# backlight_board.net
KiCad netlist of a schematic drawn in EAGLE
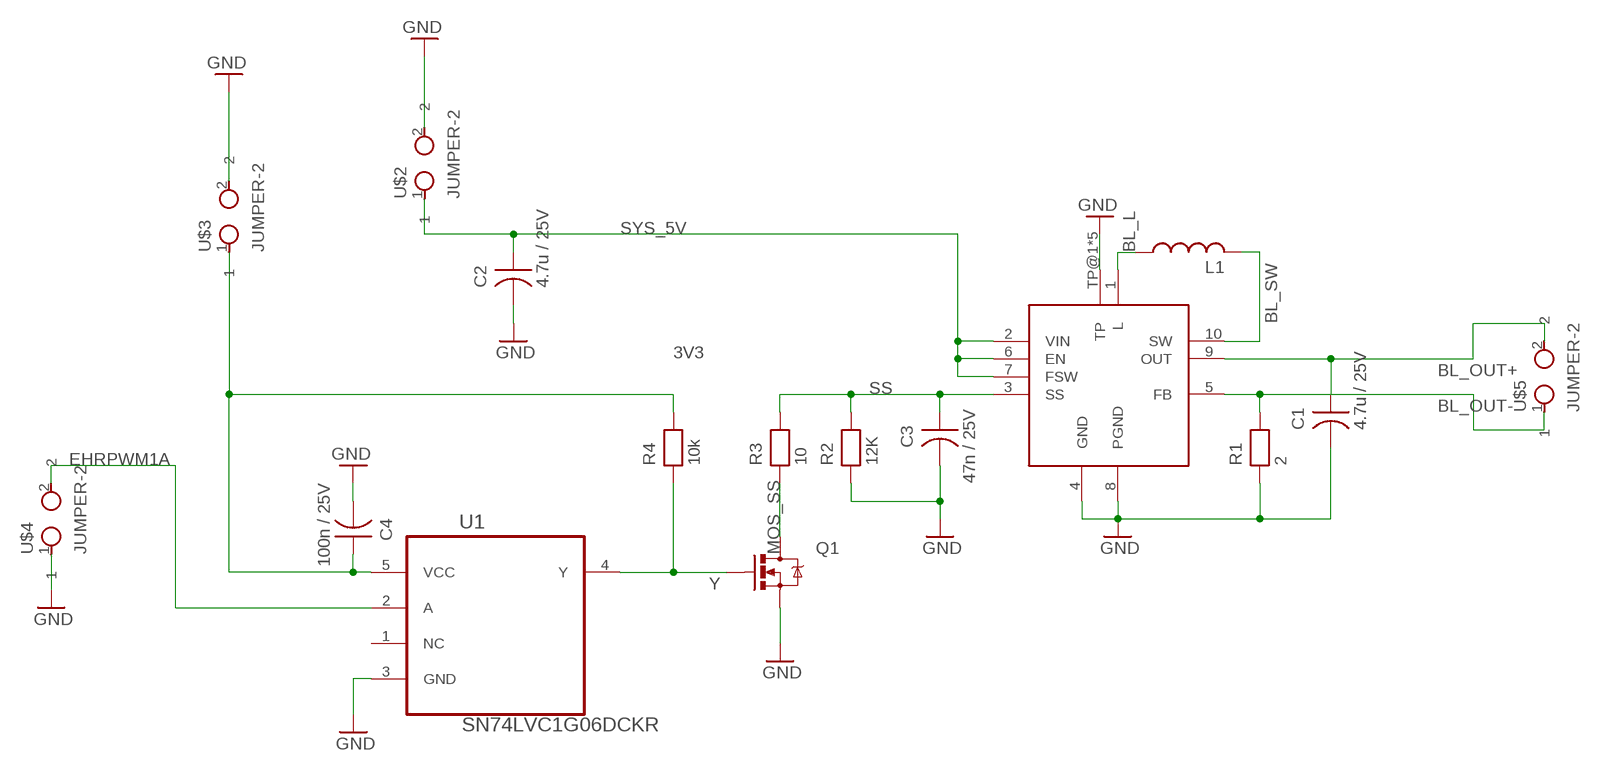
[diagram p0: schematic, sheet 1]

(export (version "E")
  (design (tool "Eeschema 10.0.6"))
  (components
    (comp (ref "C1")
      (value "4.7u / 25V")
      (footprint "eagle-import:R0805")
      (libsource (lib "eagle-import") (part "PCAP0805LEVEL3"))
    )
    (comp (ref "C2")
      (value "4.7u / 25V")
      (footprint "eagle-import:R0805")
      (libsource (lib "eagle-import") (part "PCAP0805LEVEL3"))
    )
    (comp (ref "C3")
      (value "47n / 25V")
      (footprint "eagle-import:R0603")
      (libsource (lib "eagle-import") (part "PCAP0603LEVEL3"))
    )
    (comp (ref "C4")
      (value "100n / 25V")
      (footprint "eagle-import:R0603")
      (libsource (lib "eagle-import") (part "PCAP0603LEVEL3"))
    )
    (comp (ref "L1")
      (value "L-US")
      (footprint "eagle-import:VLCF4018-2")
      (libsource (lib "eagle-import") (part "L-US"))
    )
    (comp (ref "Q1")
      (value "MOSFET-NCHANNELBSS138")
      (footprint "eagle-import:SOT23")
      (libsource (lib "eagle-import") (part "MOSFET-NCHANNELBSS138"))
    )
    (comp (ref "R1")
      (value "2")
      (footprint "eagle-import:R0603")
      (libsource (lib "eagle-import") (part "PRES0603LEVEL3"))
    )
    (comp (ref "R2")
      (value "12K")
      (footprint "eagle-import:R0603")
      (libsource (lib "eagle-import") (part "PRES0603LEVEL3"))
    )
    (comp (ref "R3")
      (value "10")
      (footprint "eagle-import:R0603")
      (libsource (lib "eagle-import") (part "PRES0603LEVEL3"))
    )
    (comp (ref "R4")
      (value "10k")
      (footprint "eagle-import:R0603")
      (libsource (lib "eagle-import") (part "PRES0603LEVEL3"))
    )
    (comp (ref "U$1")
      (value "TPS61080")
      (footprint "eagle-import:VSON-10")
      (libsource (lib "eagle-import") (part "TPS61080"))
    )
    (comp (ref "U$2")
      (value "JUMPER-2")
      (footprint "eagle-import:1X02")
      (libsource (lib "eagle-import") (part "JUMPER-2"))
    )
    (comp (ref "U$3")
      (value "JUMPER-2")
      (footprint "eagle-import:1X02")
      (libsource (lib "eagle-import") (part "JUMPER-2"))
    )
    (comp (ref "U$4")
      (value "JUMPER-2")
      (footprint "eagle-import:1X02")
      (libsource (lib "eagle-import") (part "JUMPER-2"))
    )
    (comp (ref "U$5")
      (value "JUMPER-2")
      (footprint "eagle-import:1X02")
      (libsource (lib "eagle-import") (part "JUMPER-2"))
    )
    (comp (ref "U1")
      (value "SN74LVC1G06DCKR")
      (footprint "eagle-import:SOT65P210X110-5N")
      (libsource (lib "eagle-import") (part "SN74LVC1G06DCKR"))
    )
  )
  (nets
    (net (code "1") (name "/3V3") (class "Default")
      (node (ref "C4") (pin "P$2") (pinfunction "P$2_P$2") (pintype "bidirectional"))
      (node (ref "R4") (pin "P$2") (pinfunction "P$2_P$2") (pintype "bidirectional"))
      (node (ref "U$3") (pin "1") (pinfunction "1_1") (pintype "bidirectional"))
      (node (ref "U1") (pin "5") (pinfunction "VCC_5") (pintype "power_in"))
    )
    (net (code "2") (name "/BL_L") (class "Default")
      (node (ref "L1") (pin "1") (pinfunction "1_1") (pintype "passive"))
      (node (ref "U$1") (pin "1") (pinfunction "L_1") (pintype "bidirectional"))
    )
    (net (code "3") (name "/BL_OUT+") (class "Default")
      (node (ref "C1") (pin "P$2") (pinfunction "P$2_P$2") (pintype "bidirectional"))
      (node (ref "U$1") (pin "9") (pinfunction "OUT_9") (pintype "bidirectional"))
      (node (ref "U$5") (pin "2") (pinfunction "2_2") (pintype "bidirectional"))
    )
    (net (code "4") (name "/BL_OUT-") (class "Default")
      (node (ref "R1") (pin "P$2") (pinfunction "P$2_P$2") (pintype "bidirectional"))
      (node (ref "U$1") (pin "5") (pinfunction "FB_5") (pintype "bidirectional"))
      (node (ref "U$5") (pin "1") (pinfunction "1_1") (pintype "bidirectional"))
    )
    (net (code "5") (name "/BL_SW") (class "Default")
      (node (ref "L1") (pin "2") (pinfunction "2_2") (pintype "passive"))
      (node (ref "U$1") (pin "10") (pinfunction "SW_10") (pintype "bidirectional"))
    )
    (net (code "6") (name "/EHRPWM1A") (class "Default")
      (node (ref "U$4") (pin "2") (pinfunction "2_2") (pintype "bidirectional"))
      (node (ref "U1") (pin "2") (pinfunction "A_2") (pintype "input"))
    )
    (net (code "7") (name "/MOS_SS") (class "Default")
      (node (ref "Q1") (pin "3") (pinfunction "D_3") (pintype "passive"))
      (node (ref "R3") (pin "P$1") (pinfunction "P$1_P$1") (pintype "bidirectional"))
    )
    (net (code "8") (name "/SS") (class "Default")
      (node (ref "C3") (pin "P$2") (pinfunction "P$2_P$2") (pintype "bidirectional"))
      (node (ref "R2") (pin "P$2") (pinfunction "P$2_P$2") (pintype "bidirectional"))
      (node (ref "R3") (pin "P$2") (pinfunction "P$2_P$2") (pintype "bidirectional"))
      (node (ref "U$1") (pin "3") (pinfunction "SS_3") (pintype "bidirectional"))
    )
    (net (code "9") (name "/SYS_5V") (class "Default")
      (node (ref "C2") (pin "P$2") (pinfunction "P$2_P$2") (pintype "bidirectional"))
      (node (ref "U$1") (pin "2") (pinfunction "VIN_2") (pintype "bidirectional"))
      (node (ref "U$1") (pin "6") (pinfunction "EN_6") (pintype "bidirectional"))
      (node (ref "U$1") (pin "7") (pinfunction "FSW_7") (pintype "bidirectional"))
      (node (ref "U$2") (pin "1") (pinfunction "1_1") (pintype "bidirectional"))
    )
    (net (code "10") (name "/Y") (class "Default")
      (node (ref "Q1") (pin "1") (pinfunction "G_1") (pintype "passive"))
      (node (ref "R4") (pin "P$1") (pinfunction "P$1_P$1") (pintype "bidirectional"))
      (node (ref "U1") (pin "4") (pinfunction "Y_4") (pintype "output"))
    )
    (net (code "11") (name "GND") (class "Default")
      (node (ref "C1") (pin "P$1") (pinfunction "P$1_P$1") (pintype "bidirectional"))
      (node (ref "C2") (pin "P$1") (pinfunction "P$1_P$1") (pintype "bidirectional"))
      (node (ref "C3") (pin "P$1") (pinfunction "P$1_P$1") (pintype "bidirectional"))
      (node (ref "C4") (pin "P$1") (pinfunction "P$1_P$1") (pintype "bidirectional"))
      (node (ref "Q1") (pin "2") (pinfunction "S_2") (pintype "passive"))
      (node (ref "R1") (pin "P$1") (pinfunction "P$1_P$1") (pintype "bidirectional"))
      (node (ref "R2") (pin "P$1") (pinfunction "P$1_P$1") (pintype "bidirectional"))
      (node (ref "U$1") (pin "4") (pinfunction "GND_4") (pintype "bidirectional"))
      (node (ref "U$1") (pin "8") (pinfunction "PGND_8") (pintype "bidirectional"))
      (node (ref "U$1") (pin "TP@1") (pinfunction "TP_TP@1") (pintype "bidirectional"))
      (node (ref "U$1") (pin "TP@2") (pinfunction "TP_TP@2") (pintype "bidirectional"))
      (node (ref "U$1") (pin "TP@3") (pinfunction "TP_TP@3") (pintype "bidirectional"))
      (node (ref "U$1") (pin "TP@4") (pinfunction "TP_TP@4") (pintype "bidirectional"))
      (node (ref "U$1") (pin "TP@5") (pinfunction "TP_TP@5") (pintype "bidirectional"))
      (node (ref "U$2") (pin "2") (pinfunction "2_2") (pintype "bidirectional"))
      (node (ref "U$3") (pin "2") (pinfunction "2_2") (pintype "bidirectional"))
      (node (ref "U$4") (pin "1") (pinfunction "1_1") (pintype "bidirectional"))
      (node (ref "U1") (pin "3") (pinfunction "GND_3") (pintype "passive"))
    )
    (net (code "12") (name "unconnected-(U1-NC-Pad1)") (class "Default")
      (node (ref "U1") (pin "1") (pinfunction "NC_1") (pintype "no_connect"))
    )
  )
)
